# max30105.net
KiCad netlist of a schematic drawn in EAGLE
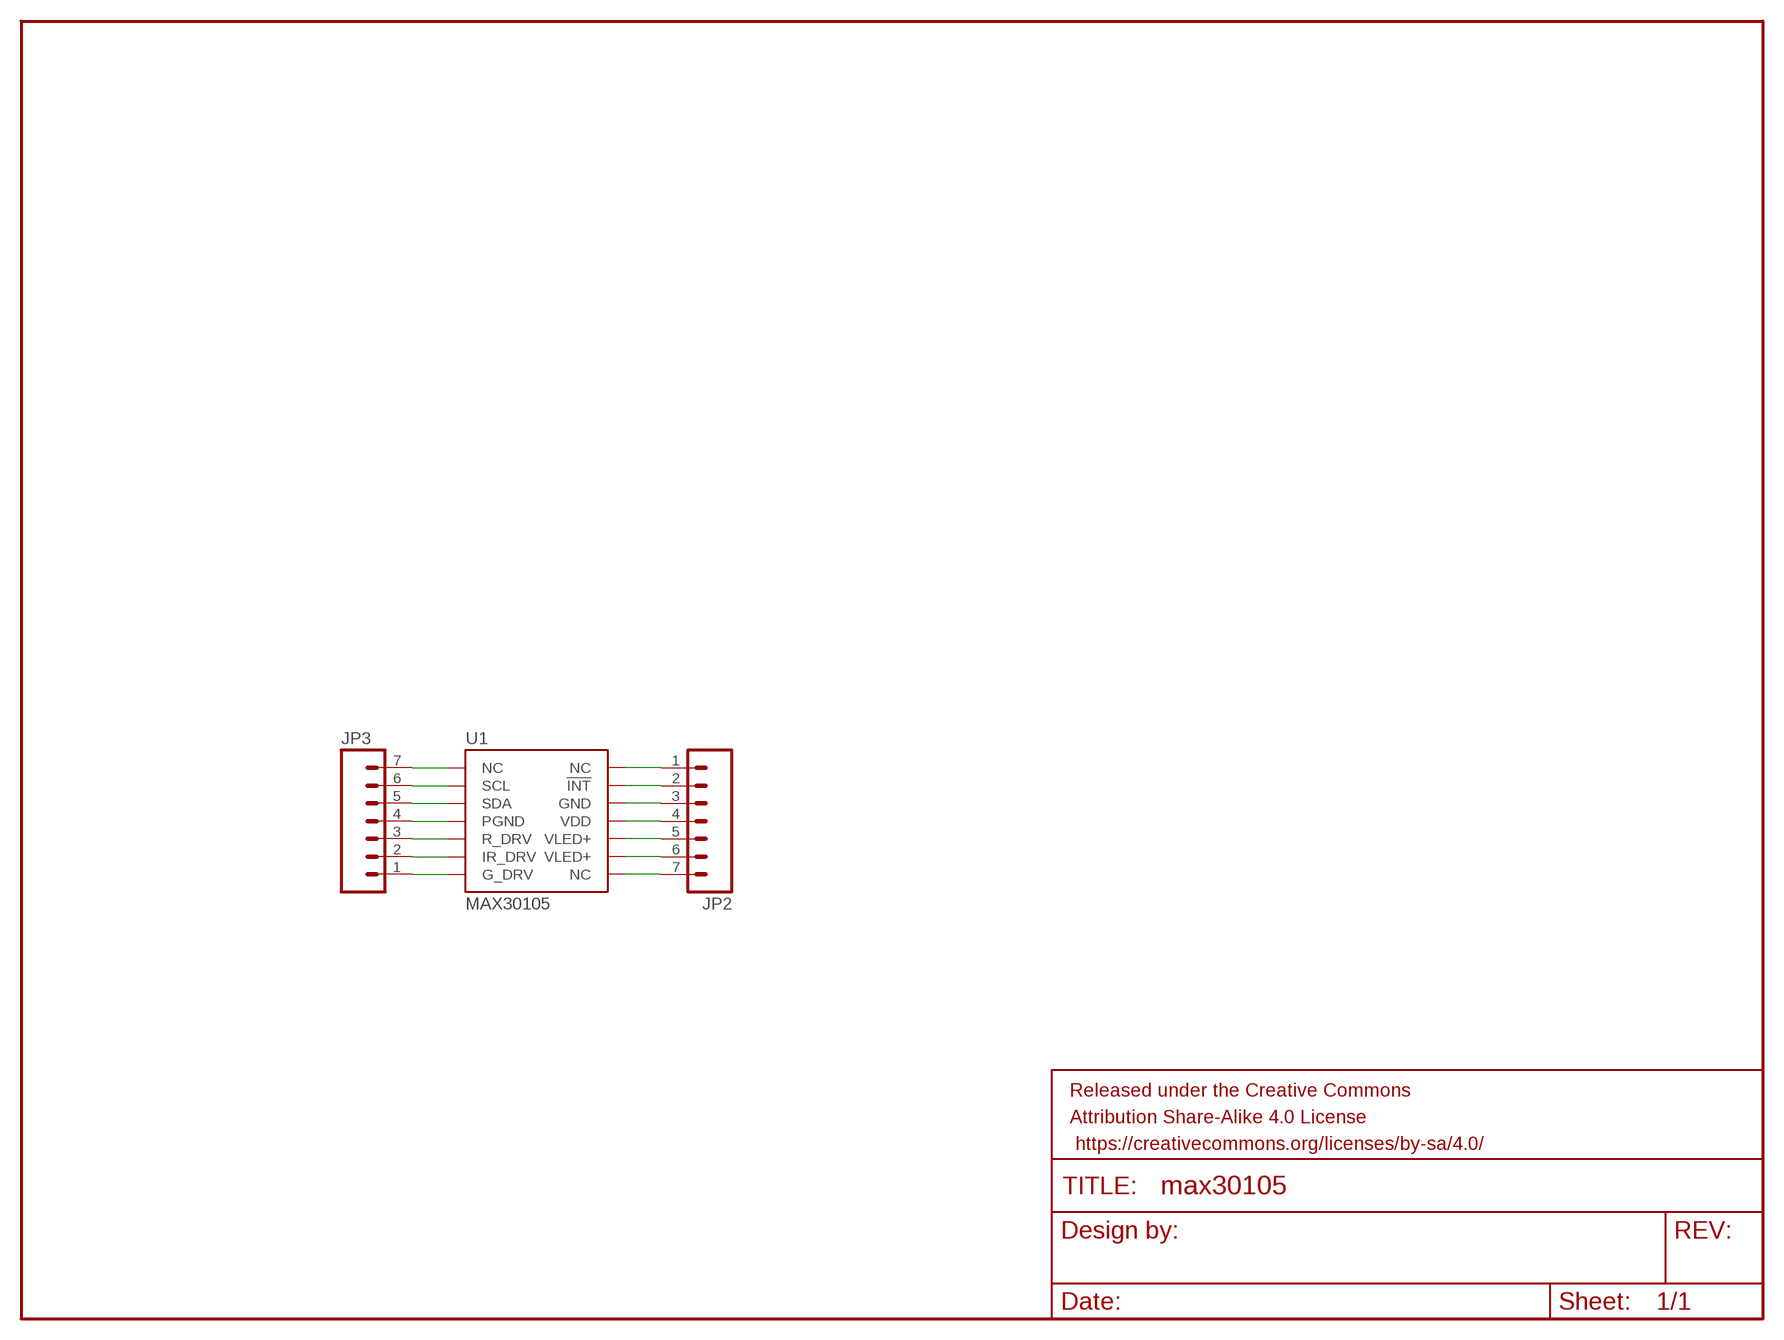
[diagram p0: schematic, sheet 1]

(export (version "E")
  (design (tool "Eeschema 10.0.6"))
  (components
    (comp (ref "FRAME1")
      (value "FRAME-LETTER")
      (footprint "eagle-import:CREATIVE_COMMONS")
      (libsource (lib "eagle-import") (part "FRAME-LETTER"))
    )
    (comp (ref "JP2")
      (value "M07")
      (footprint "eagle-import:1X07")
      (libsource (lib "eagle-import") (part "M07"))
    )
    (comp (ref "JP3")
      (value "M07")
      (footprint "eagle-import:1X07")
      (libsource (lib "eagle-import") (part "M07"))
    )
    (comp (ref "U1")
      (value "MAX30105")
      (footprint "eagle-import:OLGA-14")
      (libsource (lib "eagle-import") (part "MAX30105SMD"))
    )
  )
  (nets
    (net (code "1") (name "Net-(JP2-Pad1)") (class "Default")
      (node (ref "JP2") (pin "1") (pinfunction "1_1") (pintype "passive"))
      (node (ref "U1") (pin "14") (pinfunction "NC_14") (pintype "bidirectional"))
    )
    (net (code "2") (name "Net-(JP2-Pad5)") (class "Default")
      (node (ref "JP2") (pin "5") (pinfunction "5_5") (pintype "passive"))
      (node (ref "U1") (pin "10") (pinfunction "VLED+_10") (pintype "bidirectional"))
    )
    (net (code "3") (name "Net-(JP2-Pad6)") (class "Default")
      (node (ref "JP2") (pin "6") (pinfunction "6_6") (pintype "passive"))
      (node (ref "U1") (pin "9") (pinfunction "VLED+_9") (pintype "bidirectional"))
    )
    (net (code "4") (name "Net-(JP2-Pad7)") (class "Default")
      (node (ref "JP2") (pin "7") (pinfunction "7_7") (pintype "passive"))
      (node (ref "U1") (pin "8") (pinfunction "NC_8") (pintype "bidirectional"))
    )
    (net (code "5") (name "Net-(JP3-Pad7)") (class "Default")
      (node (ref "JP3") (pin "7") (pinfunction "7_7") (pintype "passive"))
      (node (ref "U1") (pin "1") (pinfunction "NC_1") (pintype "bidirectional"))
    )
    (net (code "6") (name "Net-(U1-GND)") (class "Default")
      (node (ref "JP2") (pin "3") (pinfunction "3_3") (pintype "passive"))
      (node (ref "U1") (pin "12") (pinfunction "GND_12") (pintype "bidirectional"))
    )
    (net (code "7") (name "Net-(U1-G_DRV)") (class "Default")
      (node (ref "JP3") (pin "1") (pinfunction "1_1") (pintype "passive"))
      (node (ref "U1") (pin "7") (pinfunction "G_DRV_7") (pintype "bidirectional"))
    )
    (net (code "8") (name "Net-(U1-IR_DRV)") (class "Default")
      (node (ref "JP3") (pin "2") (pinfunction "2_2") (pintype "passive"))
      (node (ref "U1") (pin "6") (pinfunction "IR_DRV_6") (pintype "bidirectional"))
    )
    (net (code "9") (name "Net-(U1-PGND)") (class "Default")
      (node (ref "JP3") (pin "4") (pinfunction "4_4") (pintype "passive"))
      (node (ref "U1") (pin "4") (pinfunction "PGND_4") (pintype "bidirectional"))
    )
    (net (code "10") (name "Net-(U1-R_DRV)") (class "Default")
      (node (ref "JP3") (pin "3") (pinfunction "3_3") (pintype "passive"))
      (node (ref "U1") (pin "5") (pinfunction "R_DRV_5") (pintype "bidirectional"))
    )
    (net (code "11") (name "Net-(U1-SCL)") (class "Default")
      (node (ref "JP3") (pin "6") (pinfunction "6_6") (pintype "passive"))
      (node (ref "U1") (pin "2") (pinfunction "SCL_2") (pintype "bidirectional"))
    )
    (net (code "12") (name "Net-(U1-SDA)") (class "Default")
      (node (ref "JP3") (pin "5") (pinfunction "5_5") (pintype "passive"))
      (node (ref "U1") (pin "3") (pinfunction "SDA_3") (pintype "bidirectional"))
    )
    (net (code "13") (name "Net-(U1-VDD)") (class "Default")
      (node (ref "JP2") (pin "4") (pinfunction "4_4") (pintype "passive"))
      (node (ref "U1") (pin "11") (pinfunction "VDD_11") (pintype "bidirectional"))
    )
    (net (code "14") (name "Net-(U1-~{INT})") (class "Default")
      (node (ref "JP2") (pin "2") (pinfunction "2_2") (pintype "passive"))
      (node (ref "U1") (pin "13") (pinfunction "~{INT}_13") (pintype "bidirectional"))
    )
  )
)
